# 13_-Motorcontroller.net
KiCad netlist of a schematic drawn in Altium Designer
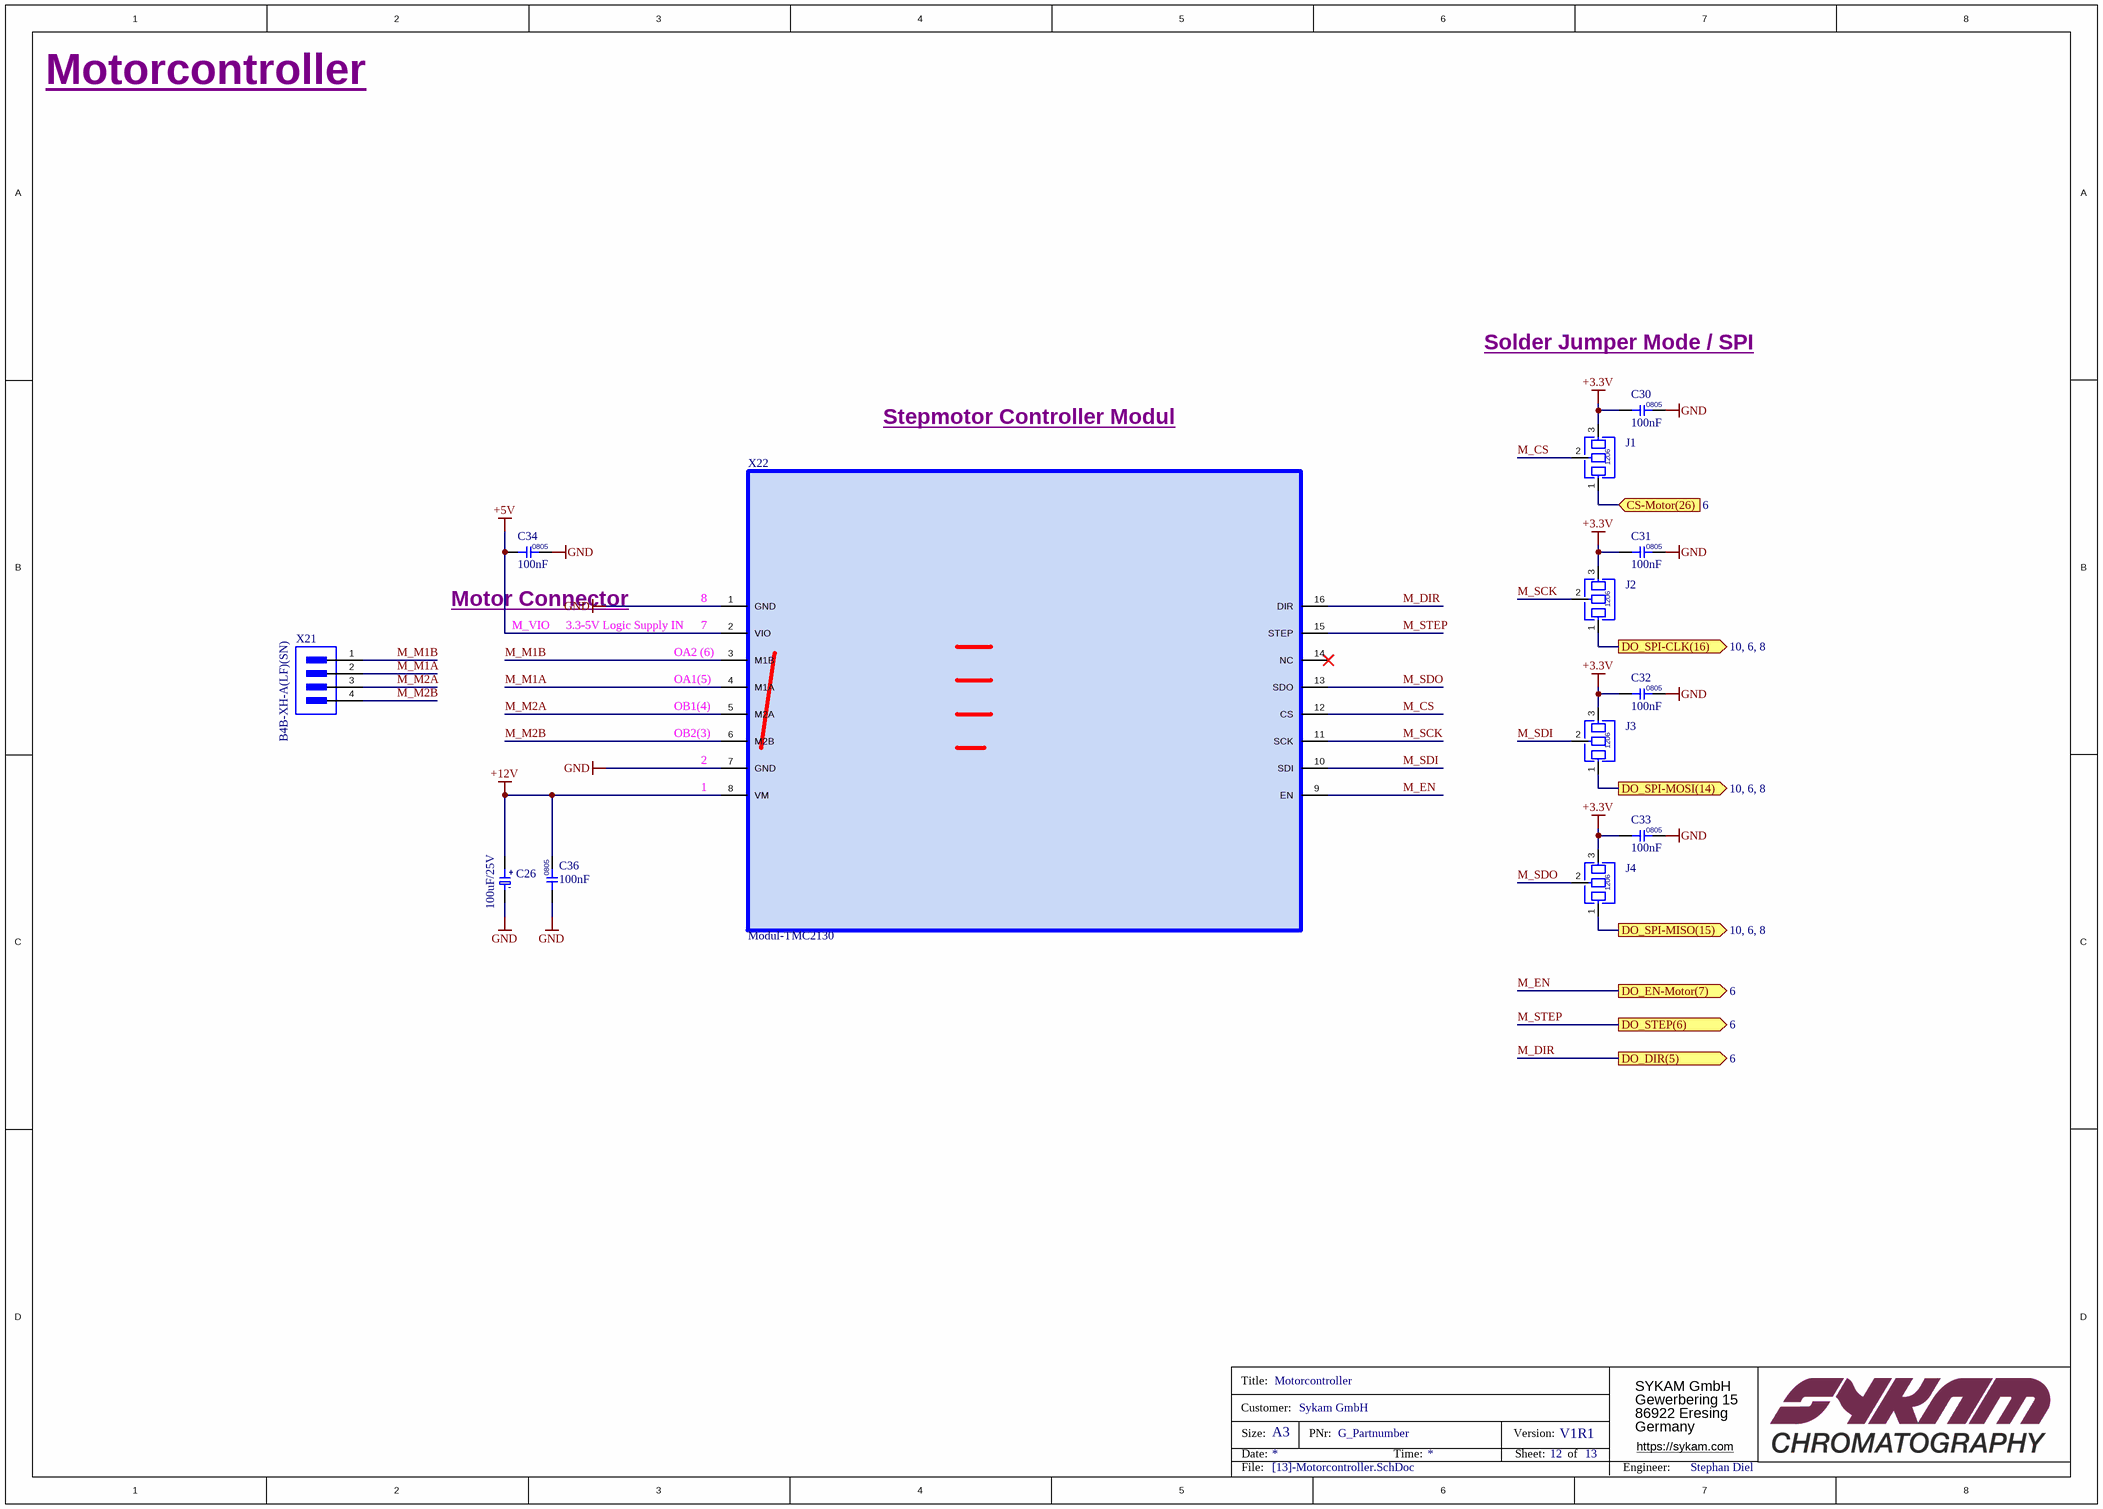
[diagram p0: [13]-Motorcontroller.SchDoc]

(export (version "E")
  (design (tool "Eeschema 10.0.6"))
  (components
    (comp (ref "C26")
      (value "100uF/25V")
      (footprint "C_A768EB107M1ELAE036-100uF")
      (description "Cap Alum Poly 100UF 20% 25V SMD")
      (fields
        (field (name "MANUFACTURER") "KEMET")
        (field (name "MANUFACTURER PART NUMBER") "A768EB107M1ELAE036")
      )
      (libsource (lib "ToradexMainBoard-V0I1") (part "C_100uF/25V_A768EB107M1ELAE036"))
    )
    (comp (ref "C30")
      (value "100nF")
      (footprint "C0805")
      (description "CAP CER 0.1UF 50V X7R 0805")
      (fields
        (field (name "MANUFACTURER PART NUMBER") "CC0805KRX7R9BB104")
        (field (name "TOLERANCE") "10%")
        (field (name "PCBCHECKED") "initials after Checked")
        (field (name "SCHCHECKED") "Initials after checked")
      )
      (libsource (lib "ToradexMainBoard-V0I1") (part "C_100nF_CC0805KRX7R9BB104"))
    )
    (comp (ref "C31")
      (value "100nF")
      (footprint "C0805")
      (description "CAP CER 0.1UF 50V X7R 0805")
      (fields
        (field (name "MANUFACTURER PART NUMBER") "CC0805KRX7R9BB104")
        (field (name "TOLERANCE") "10%")
        (field (name "PCBCHECKED") "initials after Checked")
        (field (name "SCHCHECKED") "Initials after checked")
      )
      (libsource (lib "ToradexMainBoard-V0I1") (part "C_100nF_CC0805KRX7R9BB104"))
    )
    (comp (ref "C32")
      (value "100nF")
      (footprint "C0805")
      (description "CAP CER 0.1UF 50V X7R 0805")
      (fields
        (field (name "MANUFACTURER PART NUMBER") "CC0805KRX7R9BB104")
        (field (name "TOLERANCE") "10%")
        (field (name "PCBCHECKED") "initials after Checked")
        (field (name "SCHCHECKED") "Initials after checked")
      )
      (libsource (lib "ToradexMainBoard-V0I1") (part "C_100nF_CC0805KRX7R9BB104"))
    )
    (comp (ref "C33")
      (value "100nF")
      (footprint "C0805")
      (description "CAP CER 0.1UF 50V X7R 0805")
      (fields
        (field (name "MANUFACTURER PART NUMBER") "CC0805KRX7R9BB104")
        (field (name "TOLERANCE") "10%")
        (field (name "PCBCHECKED") "initials after Checked")
        (field (name "SCHCHECKED") "Initials after checked")
      )
      (libsource (lib "ToradexMainBoard-V0I1") (part "C_100nF_CC0805KRX7R9BB104"))
    )
    (comp (ref "C34")
      (value "100nF")
      (footprint "C0805")
      (description "CAP CER 0.1UF 50V X7R 0805")
      (fields
        (field (name "MANUFACTURER PART NUMBER") "CC0805KRX7R9BB104")
        (field (name "TOLERANCE") "10%")
        (field (name "PCBCHECKED") "initials after Checked")
        (field (name "SCHCHECKED") "Initials after checked")
      )
      (libsource (lib "ToradexMainBoard-V0I1") (part "C_100nF_CC0805KRX7R9BB104"))
    )
    (comp (ref "C36")
      (value "100nF")
      (footprint "C0805")
      (description "CAP CER 0.1UF 50V X7R 0805")
      (fields
        (field (name "MANUFACTURER PART NUMBER") "CC0805KRX7R9BB104")
        (field (name "TOLERANCE") "10%")
        (field (name "PCBCHECKED") "initials after Checked")
        (field (name "SCHCHECKED") "Initials after checked")
      )
      (libsource (lib "ToradexMainBoard-V0I1") (part "C_100nF_CC0805KRX7R9BB104"))
    )
    (comp (ref "J1")
      (value "SolderJumper-no-Part")
      (footprint "SolderJumper-R1206")
      (description "SolderJumper-no-Part 1206")
      (libsource (lib "ToradexMainBoard-V0I1") (part "J_SolderJumper-no-Part"))
    )
    (comp (ref "J2")
      (value "SolderJumper-no-Part")
      (footprint "SolderJumper-R1206")
      (description "SolderJumper-no-Part 1206")
      (libsource (lib "ToradexMainBoard-V0I1") (part "J_SolderJumper-no-Part"))
    )
    (comp (ref "J3")
      (value "SolderJumper-no-Part")
      (footprint "SolderJumper-R1206")
      (description "SolderJumper-no-Part 1206")
      (libsource (lib "ToradexMainBoard-V0I1") (part "J_SolderJumper-no-Part"))
    )
    (comp (ref "J4")
      (value "SolderJumper-no-Part")
      (footprint "SolderJumper-R1206")
      (description "SolderJumper-no-Part 1206")
      (libsource (lib "ToradexMainBoard-V0I1") (part "J_SolderJumper-no-Part"))
    )
    (comp (ref "X21")
      (value "B4B-XH-A(LF)(SN)")
      (footprint "CON_B4B-XH-A(LF)(SN)")
      (fields (field (name "MANUFACTURER") "JST"))
      (libsource (lib "ToradexMainBoard-V0I1") (part "CON_4pol_B4B-XH-A(LF)(SN)"))
    )
    (comp (ref "X22")
      (value "Modul-TMC2130")
      (footprint "TMC2130-Connectors")
      (description "TMC2130STEPPERDRIVERBOARD")
      (fields
        (field (name "MANUFACTURER") "Trinamic")
        (field (name "MANUFACTURER PART NUMBER") "TMC SILENTSTEPSTICK SPI")
      )
      (libsource (lib "ToradexMainBoard-V0I1") (part "CON_Modul_TMCSILENTSTEPSTICK SPI"))
    )
  )
  (nets
    (net (code "1") (name "+3.3V") (class "Default")
      (node (ref "C30") (pin "1") (pinfunction "1_1") (pintype "passive"))
      (node (ref "C31") (pin "1") (pinfunction "1_1") (pintype "passive"))
      (node (ref "C32") (pin "1") (pinfunction "1_1") (pintype "passive"))
      (node (ref "C33") (pin "1") (pinfunction "1_1") (pintype "passive"))
      (node (ref "J1") (pin "3") (pinfunction "3_3") (pintype "passive"))
      (node (ref "J2") (pin "3") (pinfunction "3_3") (pintype "passive"))
      (node (ref "J3") (pin "3") (pinfunction "3_3") (pintype "passive"))
      (node (ref "J4") (pin "3") (pinfunction "3_3") (pintype "passive"))
    )
    (net (code "2") (name "+5V") (class "Default")
      (node (ref "C34") (pin "1") (pinfunction "1_1") (pintype "passive"))
      (node (ref "X22") (pin "2") (pinfunction "VIO_2") (pintype "passive"))
    )
    (net (code "3") (name "+12V") (class "Default")
      (node (ref "C26") (pin "1") (pinfunction "1_1") (pintype "passive"))
      (node (ref "C36") (pin "2") (pinfunction "2_2") (pintype "passive"))
      (node (ref "X22") (pin "8") (pinfunction "VM_8") (pintype "passive"))
    )
    (net (code "4") (name "/CS-Motor(26)") (class "Default")
      (node (ref "J1") (pin "1") (pinfunction "1_1") (pintype "passive"))
    )
    (net (code "5") (name "/DO_SPI-CLK(16)") (class "Default")
      (node (ref "J2") (pin "1") (pinfunction "1_1") (pintype "passive"))
    )
    (net (code "6") (name "/DO_SPI-MISO(15)") (class "Default")
      (node (ref "J4") (pin "1") (pinfunction "1_1") (pintype "passive"))
    )
    (net (code "7") (name "/DO_SPI-MOSI(14)") (class "Default")
      (node (ref "J3") (pin "1") (pinfunction "1_1") (pintype "passive"))
    )
    (net (code "8") (name "/M_CS") (class "Default")
      (node (ref "J1") (pin "2") (pinfunction "2_2") (pintype "passive"))
      (node (ref "X22") (pin "12") (pinfunction "CS_12") (pintype "passive"))
    )
    (net (code "9") (name "/M_DIR") (class "Default")
      (node (ref "X22") (pin "16") (pinfunction "DIR_16") (pintype "passive"))
    )
    (net (code "10") (name "/M_EN") (class "Default")
      (node (ref "X22") (pin "9") (pinfunction "EN_9") (pintype "passive"))
    )
    (net (code "11") (name "/M_M1A") (class "Default")
      (node (ref "X21") (pin "2") (pintype "passive"))
      (node (ref "X22") (pin "4") (pinfunction "M1A_4") (pintype "passive"))
    )
    (net (code "12") (name "/M_M1B") (class "Default")
      (node (ref "X21") (pin "1") (pintype "passive"))
      (node (ref "X22") (pin "3") (pinfunction "M1B_3") (pintype "passive"))
    )
    (net (code "13") (name "/M_M2A") (class "Default")
      (node (ref "X21") (pin "3") (pintype "passive"))
      (node (ref "X22") (pin "5") (pinfunction "M2A_5") (pintype "passive"))
    )
    (net (code "14") (name "/M_M2B") (class "Default")
      (node (ref "X21") (pin "4") (pintype "passive"))
      (node (ref "X22") (pin "6") (pinfunction "M2B_6") (pintype "passive"))
    )
    (net (code "15") (name "/M_SCK") (class "Default")
      (node (ref "J2") (pin "2") (pinfunction "2_2") (pintype "passive"))
      (node (ref "X22") (pin "11") (pinfunction "SCK_11") (pintype "passive"))
    )
    (net (code "16") (name "/M_SDI") (class "Default")
      (node (ref "J3") (pin "2") (pinfunction "2_2") (pintype "passive"))
      (node (ref "X22") (pin "10") (pinfunction "SDI_10") (pintype "passive"))
    )
    (net (code "17") (name "/M_SDO") (class "Default")
      (node (ref "J4") (pin "2") (pinfunction "2_2") (pintype "passive"))
      (node (ref "X22") (pin "13") (pinfunction "SDO_13") (pintype "passive"))
    )
    (net (code "18") (name "/M_STEP") (class "Default")
      (node (ref "X22") (pin "15") (pinfunction "STEP_15") (pintype "passive"))
    )
    (net (code "19") (name "GND") (class "Default")
      (node (ref "C26") (pin "2") (pinfunction "2_2") (pintype "passive"))
      (node (ref "C30") (pin "2") (pinfunction "2_2") (pintype "passive"))
      (node (ref "C31") (pin "2") (pinfunction "2_2") (pintype "passive"))
      (node (ref "C32") (pin "2") (pinfunction "2_2") (pintype "passive"))
      (node (ref "C33") (pin "2") (pinfunction "2_2") (pintype "passive"))
      (node (ref "C34") (pin "2") (pinfunction "2_2") (pintype "passive"))
      (node (ref "C36") (pin "1") (pinfunction "1_1") (pintype "passive"))
      (node (ref "X22") (pin "1") (pinfunction "GND_1") (pintype "passive"))
      (node (ref "X22") (pin "7") (pinfunction "GND_7") (pintype "passive"))
    )
    (net (code "20") (name "unconnected-(X22-NC-Pad14)") (class "Default")
      (node (ref "X22") (pin "14") (pinfunction "NC_14") (pintype "passive+no_connect"))
    )
  )
)
